# Fsociety_Keyboard_SCH_Main.net
KiCad netlist of a schematic drawn in Altium Designer
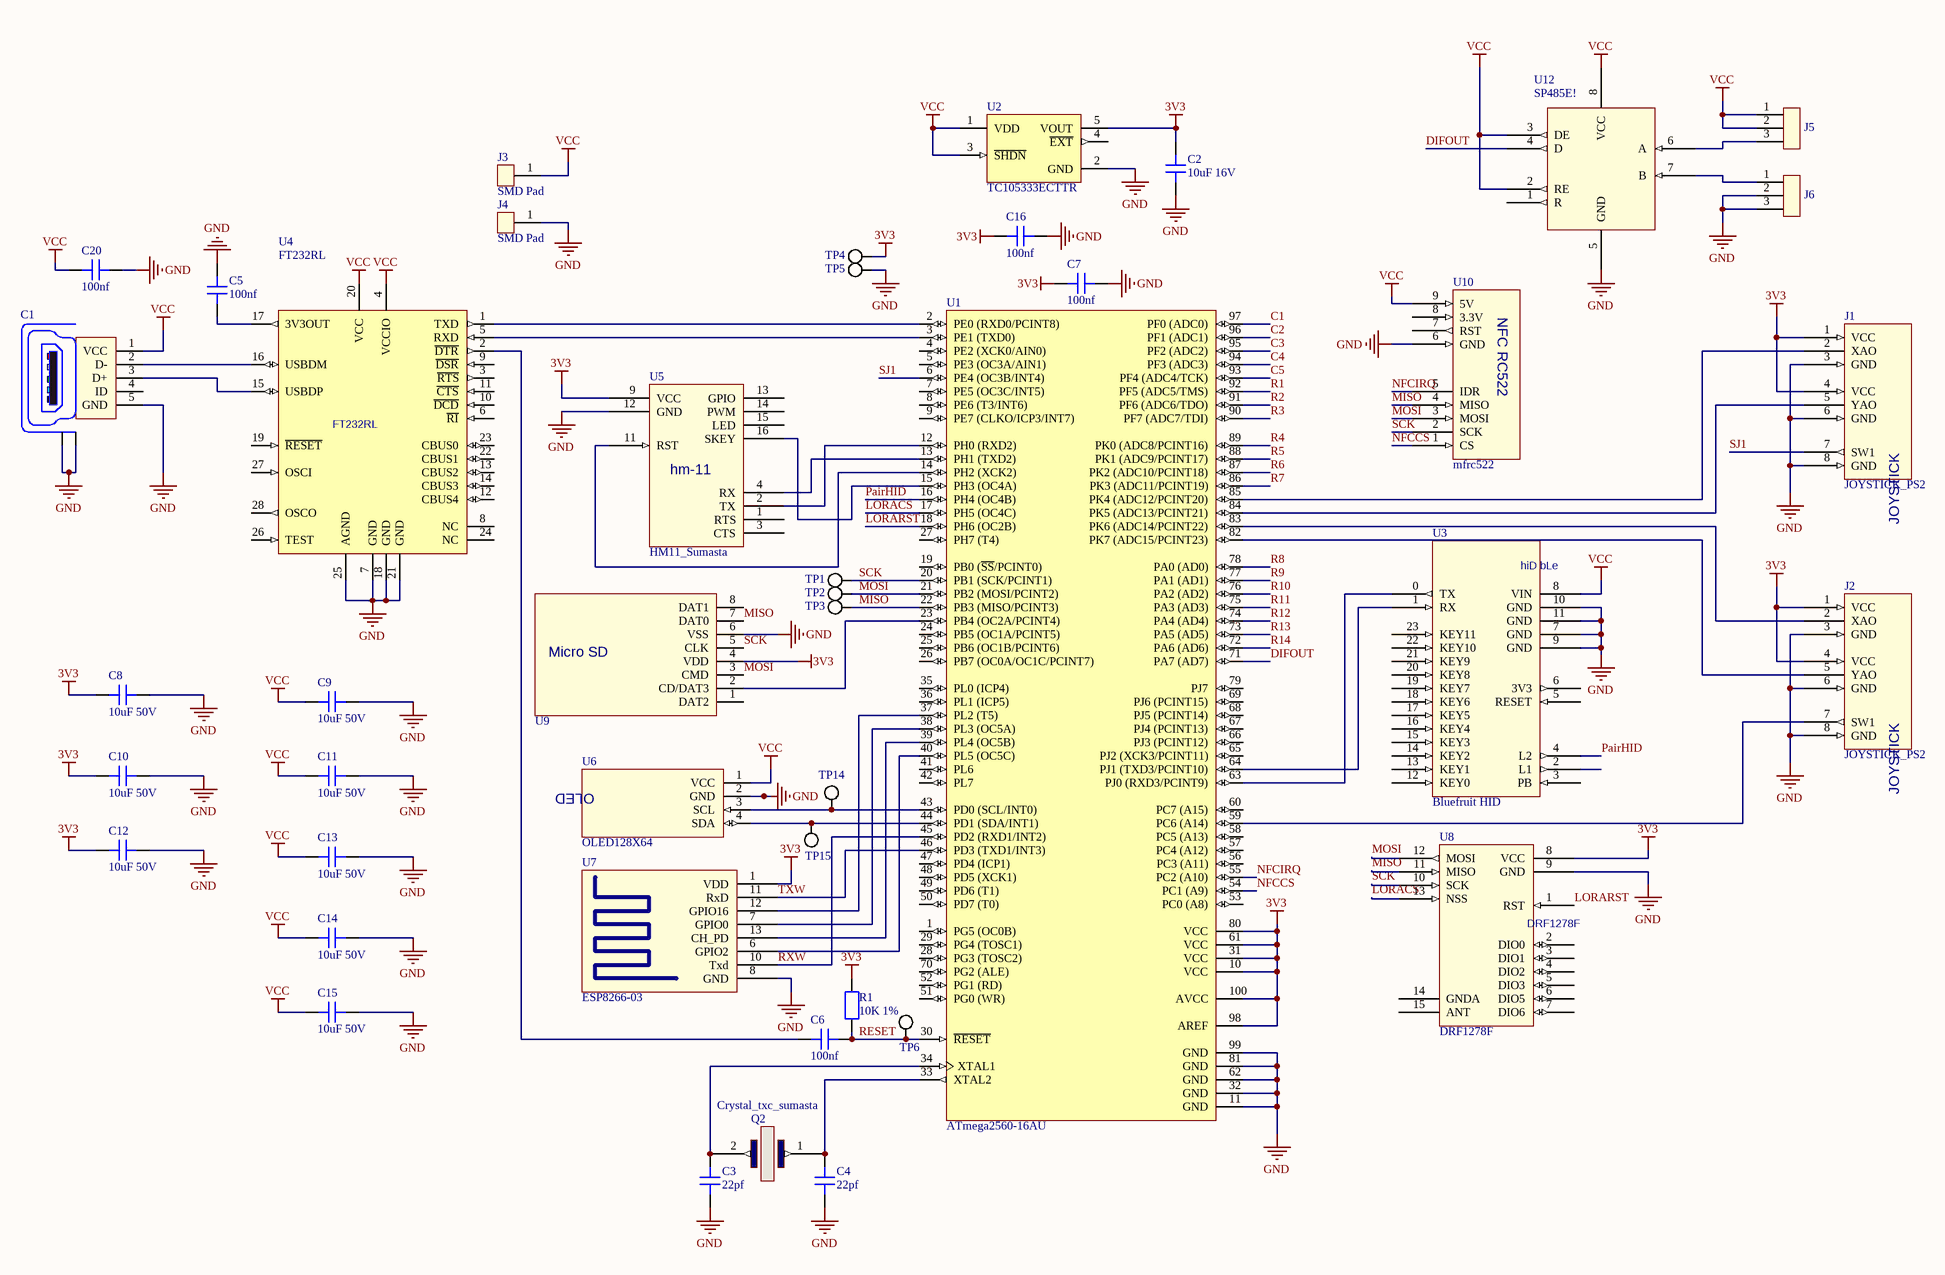
[diagram p0: Fsociety_Keyboard_SCH_Main.SchDoc]

(export (version "E")
  (design (tool "Eeschema 10.0.6"))
  (components
    (comp (ref "C1")
      (value "WR-Communication Connectors 629105150921")
      (footprint "629105150921")
      (description "WR-COM_USB_Micro Type AB_Horizontal_SMT")
      (fields
        (field (name "MANUFACTURER") "Würth Elektronik eiSos GmbH")
        (field (name "PARTNO") "629105150921")
        (field (name "CREATED BY") "Karrer Zheng")
      )
      (libsource (lib "WR-COM_Communication Connectors_rev15f") (part "WR-Communication Connectors 629105150921"))
    )
    (comp (ref "C2")
      (value "10uF 16V")
      (footprint "CAPC1608X08_NR")
      (description "Capacitor 10nF X7R ±10% 50V 0603(1608) SMD")
      (fields (field (name "MAXPARTNUMBER") "10N/50-0603!") (field (name "TOLERANCE") "±10%"))
      (libsource (lib "RENA Vault") (part "CMP-00064-A.5"))
    )
    (comp (ref "C3")
      (value "22pf")
      (footprint "CAPC1608X08_NR")
      (description "Capacitor 10nF X7R ±10% 50V 0603(1608) SMD")
      (fields (field (name "MAXPARTNUMBER") "10N/50-0603!") (field (name "TOLERANCE") "±10%"))
      (libsource (lib "RENA Vault") (part "CMP-00064-A.5"))
    )
    (comp (ref "C4")
      (value "22pf")
      (footprint "CAPC1608X08_NR")
      (description "Capacitor 10nF X7R ±10% 50V 0603(1608) SMD")
      (fields (field (name "MAXPARTNUMBER") "10N/50-0603!") (field (name "TOLERANCE") "±10%"))
      (libsource (lib "RENA Vault") (part "CMP-00064-A.5"))
    )
    (comp (ref "C5")
      (value "100nf")
      (footprint "CAPC1608X08_NR")
      (description "Capacitor 10nF X7R ±10% 50V 0603(1608) SMD")
      (fields (field (name "MAXPARTNUMBER") "10N/50-0603!") (field (name "TOLERANCE") "±10%"))
      (libsource (lib "RENA Vault") (part "CMP-00064-A.5"))
    )
    (comp (ref "C6")
      (value "100nf")
      (footprint "CAPC1608X08_NR")
      (description "Capacitor 10nF X7R ±10% 50V 0603(1608) SMD")
      (fields (field (name "MAXPARTNUMBER") "10N/50-0603!") (field (name "TOLERANCE") "±10%"))
      (libsource (lib "RENA Vault") (part "CMP-00064-A.5"))
    )
    (comp (ref "C7")
      (value "100nf")
      (footprint "CAPC1608X08_NR")
      (description "Capacitor 10nF X7R ±10% 50V 0603(1608) SMD")
      (fields (field (name "MAXPARTNUMBER") "10N/50-0603!") (field (name "TOLERANCE") "±10%"))
      (libsource (lib "RENA Vault") (part "CMP-00064-A.5"))
    )
    (comp (ref "C8")
      (value "10uF 50V")
      (footprint "CAPC3216X09_MW")
      (description "Capacitor 10uF X5R ±20% 50V 1206(3216) SMD")
      (fields (field (name "VOLTAGE") "50V") (field (name "TOLERANCE") "±20%"))
      (libsource (lib "RENA Vault") (part "Cer.Cap"))
    )
    (comp (ref "C9")
      (value "10uF 50V")
      (footprint "CAPC3216X09_MW")
      (description "Capacitor 10uF X5R ±20% 50V 1206(3216) SMD")
      (fields (field (name "VOLTAGE") "50V") (field (name "TOLERANCE") "±20%"))
      (libsource (lib "RENA Vault") (part "Cer.Cap"))
    )
    (comp (ref "C10")
      (value "10uF 50V")
      (footprint "CAPC3216X09_MW")
      (description "Capacitor 10uF X5R ±20% 50V 1206(3216) SMD")
      (fields (field (name "VOLTAGE") "50V") (field (name "TOLERANCE") "±20%"))
      (libsource (lib "RENA Vault") (part "Cer.Cap"))
    )
    (comp (ref "C11")
      (value "10uF 50V")
      (footprint "CAPC3216X09_MW")
      (description "Capacitor 10uF X5R ±20% 50V 1206(3216) SMD")
      (fields (field (name "VOLTAGE") "50V") (field (name "TOLERANCE") "±20%"))
      (libsource (lib "RENA Vault") (part "Cer.Cap"))
    )
    (comp (ref "C12")
      (value "10uF 50V")
      (footprint "CAPC3216X09_MW")
      (description "Capacitor 10uF X5R ±20% 50V 1206(3216) SMD")
      (fields (field (name "VOLTAGE") "50V") (field (name "TOLERANCE") "±20%"))
      (libsource (lib "RENA Vault") (part "Cer.Cap"))
    )
    (comp (ref "C13")
      (value "10uF 50V")
      (footprint "CAPC3216X09_MW")
      (description "Capacitor 10uF X5R ±20% 50V 1206(3216) SMD")
      (fields (field (name "VOLTAGE") "50V") (field (name "TOLERANCE") "±20%"))
      (libsource (lib "RENA Vault") (part "Cer.Cap"))
    )
    (comp (ref "C14")
      (value "10uF 50V")
      (footprint "CAPC3216X09_MW")
      (description "Capacitor 10uF X5R ±20% 50V 1206(3216) SMD")
      (fields (field (name "VOLTAGE") "50V") (field (name "TOLERANCE") "±20%"))
      (libsource (lib "RENA Vault") (part "Cer.Cap"))
    )
    (comp (ref "C15")
      (value "10uF 50V")
      (footprint "CAPC3216X09_MW")
      (description "Capacitor 10uF X5R ±20% 50V 1206(3216) SMD")
      (fields (field (name "VOLTAGE") "50V") (field (name "TOLERANCE") "±20%"))
      (libsource (lib "RENA Vault") (part "Cer.Cap"))
    )
    (comp (ref "C16")
      (value "100nf")
      (footprint "CAPC1608X08_NR")
      (description "Capacitor 10nF X7R ±10% 50V 0603(1608) SMD")
      (fields (field (name "MAXPARTNUMBER") "10N/50-0603!") (field (name "TOLERANCE") "±10%"))
      (libsource (lib "RENA Vault") (part "CMP-00064-A.5"))
    )
    (comp (ref "C20")
      (value "100nf")
      (footprint "CAPC1608X08_NR")
      (description "Capacitor 10nF X7R ±10% 50V 0603(1608) SMD")
      (fields (field (name "MAXPARTNUMBER") "10N/50-0603!") (field (name "TOLERANCE") "±10%"))
      (libsource (lib "RENA Vault") (part "CMP-00064-A.5"))
    )
    (comp (ref "J1")
      (value "JOYSTICK_PS2")
      (footprint "JOYSTICK")
      (libsource (lib "Sumasta_new") (part "JOYSTICK_PS2"))
    )
    (comp (ref "J2")
      (value "JOYSTICK_PS2")
      (footprint "JOYSTICK")
      (libsource (lib "Sumasta_new") (part "JOYSTICK_PS2"))
    )
    (comp (ref "J3")
      (value "SMD Pad")
      (footprint "CON_SMDPAD_10X5")
      (description "SMD PAD DIFFERENT SHAPES")
      (fields (field (name "MAXPARTNUMBER") "PAD_SMD!#"))
      (libsource (lib "RENA Vault") (part "CMP-00667-A.10"))
    )
    (comp (ref "J4")
      (value "SMD Pad")
      (footprint "CON_SMDPAD_10X5")
      (description "SMD PAD DIFFERENT SHAPES")
      (fields (field (name "MAXPARTNUMBER") "PAD_SMD!#"))
      (libsource (lib "RENA Vault") (part "CMP-00667-A.10"))
    )
    (comp (ref "J5")
      (value "BB02-HA031-KB1-100/33/D1")
      (footprint "FCI_77315-134-03LF")
      (description "Unshrouded header 3-pin right angle")
      (fields (field (name "MAXPARTNUMBER") "CON-BB02-HA031"))
      (libsource (lib "RENA Vault") (part "CMP-01396-A.1"))
    )
    (comp (ref "J6")
      (value "BB02-HA031-KB1-100/33/D1")
      (footprint "FCI_77315-134-03LF")
      (description "Unshrouded header 3-pin right angle")
      (fields (field (name "MAXPARTNUMBER") "CON-BB02-HA031"))
      (libsource (lib "RENA Vault") (part "CMP-01396-A.1"))
    )
    (comp (ref "Q2")
      (value "Crystal_txc_sumasta")
      (footprint "Crystal_txc_sumasta")
      (libsource (lib "Sumasta_new") (part "Crystal_txc_sumasta"))
    )
    (comp (ref "R1")
      (value "10K 1%")
      (footprint "RESC1608X06_NR")
      (description "10K  0.1W 1% 0603(1608 Metric) SMD")
      (fields (field (name "MAXPARTNUMBER") "10K-0603!") (field (name "POWER") "0.1W"))
      (libsource (lib "RENA Vault") (part "RES"))
    )
    (comp (ref "TP1")
      (value "TP")
      (footprint "TESTPAD-2MM")
      (description "TESTPOINT")
      (fields (field (name "MAXPARTNUMBER") "TP#"))
      (libsource (lib "RENA Vault") (part "CMP-00759-A.11"))
    )
    (comp (ref "TP2")
      (value "TP")
      (footprint "TESTPAD-2MM")
      (description "TESTPOINT")
      (fields (field (name "MAXPARTNUMBER") "TP#"))
      (libsource (lib "RENA Vault") (part "CMP-00759-A.11"))
    )
    (comp (ref "TP3")
      (value "TP")
      (footprint "TESTPAD-2MM")
      (description "TESTPOINT")
      (fields (field (name "MAXPARTNUMBER") "TP#"))
      (libsource (lib "RENA Vault") (part "CMP-00759-A.11"))
    )
    (comp (ref "TP4")
      (value "TP")
      (footprint "TESTPAD-2MM")
      (description "TESTPOINT")
      (fields (field (name "MAXPARTNUMBER") "TP#"))
      (libsource (lib "RENA Vault") (part "CMP-00759-A.11"))
    )
    (comp (ref "TP5")
      (value "TP")
      (footprint "TESTPAD-2MM")
      (description "TESTPOINT")
      (fields (field (name "MAXPARTNUMBER") "TP#"))
      (libsource (lib "RENA Vault") (part "CMP-00759-A.11"))
    )
    (comp (ref "TP6")
      (value "TP")
      (footprint "TESTPAD-2MM")
      (description "TESTPOINT")
      (fields (field (name "MAXPARTNUMBER") "TP#"))
      (libsource (lib "RENA Vault") (part "CMP-00759-A.11"))
    )
    (comp (ref "TP14")
      (value "TP")
      (footprint "TESTPAD-2MM")
      (description "TESTPOINT")
      (fields (field (name "MAXPARTNUMBER") "TP#"))
      (libsource (lib "RENA Vault") (part "CMP-00759-A.11"))
    )
    (comp (ref "TP15")
      (value "TP")
      (footprint "TESTPAD-2MM")
      (description "TESTPOINT")
      (fields (field (name "MAXPARTNUMBER") "TP#"))
      (libsource (lib "RENA Vault") (part "CMP-00759-A.11"))
    )
    (comp (ref "U1")
      (value "ATmega2560-16AU")
      (footprint "100A_N")
      (libsource (lib "Atmel Microcontroller megaAVR") (part "ATmega2560-16AU"))
    )
    (comp (ref "U2")
      (value "TC105333ECTTR")
      (footprint "SOT-23-CT5_N")
      (fields (field (name "MANUFACTURER") "Microchip"))
      (libsource (lib "Microchip Power Management Switching Regulator") (part "TC105333ECTTR"))
    )
    (comp (ref "U3")
      (value "Bluefruit HID")
      (footprint "BLuefruit HID")
      (libsource (lib "Sumasta_new") (part "Bluefruit HID"))
    )
    (comp (ref "U4") (value "FT232RL") (footprint "SSPO28") (libsource (lib "Sumasta_new") (part "FT232RL")))
    (comp (ref "U5")
      (value "HM11_Sumasta")
      (footprint "HM11_Sumasta")
      (libsource (lib "Sumasta_new") (part "HM11_Sumasta"))
    )
    (comp (ref "U6")
      (value "OLED128X64")
      (footprint "OLED128x64")
      (libsource (lib "Sumasta_new") (part "OLED128X64"))
    )
    (comp (ref "U7")
      (value "ESP8266-03")
      (footprint "ESP8266-03")
      (libsource (lib "Sumasta_new") (part "ESP8266-03"))
    )
    (comp (ref "U8")
      (value "DRF1278F")
      (footprint "DRF1278F")
      (libsource (lib "Sumasta_new") (part "DRF1278F"))
    )
    (comp (ref "U9")
      (value "Micro SD Connector - Hinge")
      (footprint "Micro SD Socket")
      (libsource (lib "Sumasta_new") (part "MicroSD Socket"))
    )
    (comp (ref "U10")
      (value "mfrc522")
      (footprint "MFRC522")
      (libsource (lib "Sumasta_new") (part "mfrc522"))
    )
    (comp (ref "U12")
      (value "RS485 Buffer Transceiver")
      (footprint "SOIC127P600-8N")
      (fields (field (name "MAXPARTNUMBER") "SP485E!"))
      (libsource (lib "Sumasta_new") (part "SN75176"))
    )
  )
  (nets
    (net (code "1") (name "/C1") (class "Default")
      (node (ref "U1") (pin "97") (pinfunction "PF0_(ADC0)_97") (pintype "bidirectional"))
    )
    (net (code "2") (name "/C2") (class "Default")
      (node (ref "U1") (pin "96") (pinfunction "PF1_(ADC1)_96") (pintype "bidirectional"))
    )
    (net (code "3") (name "/C3") (class "Default")
      (node (ref "U1") (pin "95") (pinfunction "PF2_(ADC2)_95") (pintype "bidirectional"))
    )
    (net (code "4") (name "/C4") (class "Default")
      (node (ref "U1") (pin "94") (pinfunction "PF3_(ADC3)_94") (pintype "bidirectional"))
    )
    (net (code "5") (name "/C5") (class "Default")
      (node (ref "U1") (pin "93") (pinfunction "PF4_(ADC4/TCK)_93") (pintype "bidirectional"))
    )
    (net (code "6") (name "/DIFOUT") (class "Default")
      (node (ref "U1") (pin "71") (pinfunction "PA7_(AD7)_71") (pintype "bidirectional"))
      (node (ref "U12") (pin "4") (pinfunction "D_4") (pintype "output"))
    )
    (net (code "7") (name "/LORACS") (class "Default")
      (node (ref "U1") (pin "17") (pinfunction "PH5_(OC4C)_17") (pintype "bidirectional"))
      (node (ref "U8") (pin "13") (pinfunction "NSS_13") (pintype "input"))
    )
    (net (code "8") (name "/LORARST") (class "Default")
      (node (ref "U1") (pin "18") (pinfunction "PH6_(OC2B)_18") (pintype "bidirectional"))
      (node (ref "U8") (pin "1") (pinfunction "RST_1") (pintype "input"))
    )
    (net (code "9") (name "/MISO") (class "Default")
      (node (ref "TP3") (pin "1") (pinfunction "1_1") (pintype "passive"))
      (node (ref "U1") (pin "22") (pinfunction "PB3_(MISO/PCINT3)_22") (pintype "bidirectional"))
      (node (ref "U10") (pin "4") (pinfunction "MISO_4") (pintype "input"))
      (node (ref "U8") (pin "11") (pinfunction "MISO_11") (pintype "input"))
      (node (ref "U9") (pin "7") (pinfunction "DAT0_7") (pintype "passive"))
    )
    (net (code "10") (name "/MOSI") (class "Default")
      (node (ref "TP2") (pin "1") (pinfunction "1_1") (pintype "passive"))
      (node (ref "U1") (pin "21") (pinfunction "PB2_(MOSI/PCINT2)_21") (pintype "bidirectional"))
      (node (ref "U10") (pin "3") (pinfunction "MOSI_3") (pintype "input"))
      (node (ref "U8") (pin "12") (pinfunction "MOSI_12") (pintype "output"))
      (node (ref "U9") (pin "3") (pinfunction "CMD_3") (pintype "passive"))
    )
    (net (code "11") (name "/NFCCS") (class "Default")
      (node (ref "U1") (pin "54") (pinfunction "PC1_(A9)_54") (pintype "bidirectional"))
      (node (ref "U10") (pin "1") (pinfunction "CS_1") (pintype "input"))
    )
    (net (code "12") (name "/NFCIRQ") (class "Default")
      (node (ref "U1") (pin "55") (pinfunction "PC2_(A10)_55") (pintype "bidirectional"))
      (node (ref "U10") (pin "5") (pinfunction "IDR_5") (pintype "passive"))
    )
    (net (code "13") (name "/PairHID") (class "Default")
      (node (ref "U1") (pin "16") (pinfunction "PH4_(OC4B)_16") (pintype "bidirectional"))
      (node (ref "U3") (pin "4") (pinfunction "L2_4") (pintype "output"))
    )
    (net (code "14") (name "/R1") (class "Default")
      (node (ref "U1") (pin "92") (pinfunction "PF5_(ADC5/TMS)_92") (pintype "bidirectional"))
    )
    (net (code "15") (name "/R2") (class "Default")
      (node (ref "U1") (pin "91") (pinfunction "PF6_(ADC6/TDO)_91") (pintype "bidirectional"))
    )
    (net (code "16") (name "/R3") (class "Default")
      (node (ref "U1") (pin "90") (pinfunction "PF7_(ADC7/TDI)_90") (pintype "bidirectional"))
    )
    (net (code "17") (name "/R4") (class "Default")
      (node (ref "U1") (pin "89") (pinfunction "PK0_(ADC8/PCINT16)_89") (pintype "bidirectional"))
    )
    (net (code "18") (name "/R5") (class "Default")
      (node (ref "U1") (pin "88") (pinfunction "PK1_(ADC9/PCINT17)_88") (pintype "bidirectional"))
    )
    (net (code "19") (name "/R6") (class "Default")
      (node (ref "U1") (pin "87") (pinfunction "PK2_(ADC10/PCINT18)_87") (pintype "bidirectional"))
    )
    (net (code "20") (name "/R7") (class "Default")
      (node (ref "U1") (pin "86") (pinfunction "PK3_(ADC11/PCINT19)_86") (pintype "bidirectional"))
    )
    (net (code "21") (name "/R8") (class "Default")
      (node (ref "U1") (pin "78") (pinfunction "PA0_(AD0)_78") (pintype "bidirectional"))
    )
    (net (code "22") (name "/R9") (class "Default")
      (node (ref "U1") (pin "77") (pinfunction "PA1_(AD1)_77") (pintype "bidirectional"))
    )
    (net (code "23") (name "/R10") (class "Default")
      (node (ref "U1") (pin "76") (pinfunction "PA2_(AD2)_76") (pintype "bidirectional"))
    )
    (net (code "24") (name "/R11") (class "Default")
      (node (ref "U1") (pin "75") (pinfunction "PA3_(AD3)_75") (pintype "bidirectional"))
    )
    (net (code "25") (name "/R12") (class "Default")
      (node (ref "U1") (pin "74") (pinfunction "PA4_(AD4)_74") (pintype "bidirectional"))
    )
    (net (code "26") (name "/R13") (class "Default")
      (node (ref "U1") (pin "73") (pinfunction "PA5_(AD5)_73") (pintype "bidirectional"))
    )
    (net (code "27") (name "/R14") (class "Default")
      (node (ref "U1") (pin "72") (pinfunction "PA6_(AD6)_72") (pintype "bidirectional"))
    )
    (net (code "28") (name "/RESET") (class "Default")
      (node (ref "C6") (pin "2") (pinfunction "2_2") (pintype "passive"))
      (node (ref "R1") (pin "1") (pinfunction "1_1") (pintype "passive"))
      (node (ref "TP6") (pin "1") (pinfunction "1_1") (pintype "passive"))
      (node (ref "U1") (pin "30") (pinfunction "~{RESET}_30") (pintype "input"))
    )
    (net (code "29") (name "/RXW") (class "Default")
      (node (ref "U1") (pin "45") (pinfunction "PD2_(RXD1/INT2)_45") (pintype "bidirectional"))
      (node (ref "U7") (pin "10") (pinfunction "Txd_10") (pintype "passive"))
    )
    (net (code "30") (name "/SCK") (class "Default")
      (node (ref "TP1") (pin "1") (pinfunction "1_1") (pintype "passive"))
      (node (ref "U1") (pin "20") (pinfunction "PB1_(SCK/PCINT1)_20") (pintype "bidirectional"))
      (node (ref "U10") (pin "2") (pinfunction "SCK_2") (pintype "passive"))
      (node (ref "U8") (pin "10") (pinfunction "SCK_10") (pintype "input"))
      (node (ref "U9") (pin "5") (pinfunction "CLK_5") (pintype "passive"))
    )
    (net (code "31") (name "/SJ1") (class "Default")
      (node (ref "J1") (pin "7") (pinfunction "SW1_7") (pintype "output"))
      (node (ref "U1") (pin "6") (pinfunction "PE4_(OC3B/INT4)_6") (pintype "bidirectional"))
    )
    (net (code "32") (name "/TXW") (class "Default")
      (node (ref "U1") (pin "46") (pinfunction "PD3_(TXD1/INT3)_46") (pintype "bidirectional"))
      (node (ref "U7") (pin "11") (pinfunction "RxD_11") (pintype "passive"))
    )
    (net (code "33") (name "3V3") (class "Default")
      (node (ref "C10") (pin "1") (pinfunction "1_1") (pintype "passive"))
      (node (ref "C12") (pin "1") (pinfunction "1_1") (pintype "passive"))
      (node (ref "C16") (pin "1") (pinfunction "1_1") (pintype "passive"))
      (node (ref "C2") (pin "2") (pinfunction "2_2") (pintype "passive"))
      (node (ref "C7") (pin "1") (pinfunction "1_1") (pintype "passive"))
      (node (ref "C8") (pin "1") (pinfunction "1_1") (pintype "passive"))
      (node (ref "J1") (pin "1") (pinfunction "VCC_1") (pintype "input"))
      (node (ref "J1") (pin "4") (pinfunction "VCC_4") (pintype "input"))
      (node (ref "J2") (pin "1") (pinfunction "VCC_1") (pintype "input"))
      (node (ref "J2") (pin "4") (pinfunction "VCC_4") (pintype "input"))
      (node (ref "R1") (pin "2") (pinfunction "2_2") (pintype "passive"))
      (node (ref "TP4") (pin "1") (pinfunction "1_1") (pintype "passive"))
      (node (ref "U1") (pin "10") (pinfunction "VCC_10") (pintype "power_in"))
      (node (ref "U1") (pin "100") (pinfunction "AVCC_100") (pintype "power_in"))
      (node (ref "U1") (pin "31") (pinfunction "VCC_31") (pintype "power_in"))
      (node (ref "U1") (pin "61") (pinfunction "VCC_61") (pintype "power_in"))
      (node (ref "U1") (pin "80") (pinfunction "VCC_80") (pintype "power_in"))
      (node (ref "U1") (pin "98") (pinfunction "AREF_98") (pintype "power_in"))
      (node (ref "U2") (pin "5") (pinfunction "VOUT_5") (pintype "power_in"))
      (node (ref "U5") (pin "9") (pinfunction "VCC_9") (pintype "power_in"))
      (node (ref "U7") (pin "1") (pinfunction "VDD_1") (pintype "passive"))
      (node (ref "U8") (pin "8") (pinfunction "VCC_8") (pintype "power_in"))
      (node (ref "U9") (pin "4") (pinfunction "VDD_4") (pintype "passive"))
    )
    (net (code "34") (name "GND") (class "Default")
      (node (ref "C1") (pin "5") (pinfunction "GND_5") (pintype "passive"))
      (node (ref "C1") (pin "Z1") (pinfunction "Shield_Z1") (pintype "passive"))
      (node (ref "C1") (pin "Z2") (pinfunction "Shield_Z2") (pintype "passive"))
      (node (ref "C10") (pin "2") (pinfunction "2_2") (pintype "passive"))
      (node (ref "C11") (pin "2") (pinfunction "2_2") (pintype "passive"))
      (node (ref "C12") (pin "2") (pinfunction "2_2") (pintype "passive"))
      (node (ref "C13") (pin "2") (pinfunction "2_2") (pintype "passive"))
      (node (ref "C14") (pin "2") (pinfunction "2_2") (pintype "passive"))
      (node (ref "C15") (pin "2") (pinfunction "2_2") (pintype "passive"))
      (node (ref "C16") (pin "2") (pinfunction "2_2") (pintype "passive"))
      (node (ref "C2") (pin "1") (pinfunction "1_1") (pintype "passive"))
      (node (ref "C20") (pin "1") (pinfunction "1_1") (pintype "passive"))
      (node (ref "C3") (pin "1") (pinfunction "1_1") (pintype "passive"))
      (node (ref "C4") (pin "1") (pinfunction "1_1") (pintype "passive"))
      (node (ref "C5") (pin "2") (pinfunction "2_2") (pintype "passive"))
      (node (ref "C7") (pin "2") (pinfunction "2_2") (pintype "passive"))
      (node (ref "C8") (pin "2") (pinfunction "2_2") (pintype "passive"))
      (node (ref "C9") (pin "2") (pinfunction "2_2") (pintype "passive"))
      (node (ref "J1") (pin "3") (pinfunction "GND_3") (pintype "input"))
      (node (ref "J1") (pin "6") (pinfunction "GND_6") (pintype "input"))
      (node (ref "J1") (pin "8") (pinfunction "GND_8") (pintype "input"))
      (node (ref "J2") (pin "3") (pinfunction "GND_3") (pintype "input"))
      (node (ref "J2") (pin "6") (pinfunction "GND_6") (pintype "input"))
      (node (ref "J2") (pin "8") (pinfunction "GND_8") (pintype "input"))
      (node (ref "J4") (pin "1") (pintype "passive"))
      (node (ref "J6") (pin "2") (pintype "passive"))
      (node (ref "J6") (pin "3") (pintype "passive"))
      (node (ref "TP5") (pin "1") (pinfunction "1_1") (pintype "passive"))
      (node (ref "U1") (pin "11") (pinfunction "GND_11") (pintype "power_in"))
      (node (ref "U1") (pin "32") (pinfunction "GND_32") (pintype "power_in"))
      (node (ref "U1") (pin "62") (pinfunction "GND_62") (pintype "power_in"))
      (node (ref "U1") (pin "81") (pinfunction "GND_81") (pintype "power_in"))
      (node (ref "U1") (pin "99") (pinfunction "GND_99") (pintype "power_in"))
      (node (ref "U10") (pin "6") (pinfunction "GND_6") (pintype "input"))
      (node (ref "U12") (pin "5") (pinfunction "GND_5") (pintype "power_in"))
      (node (ref "U2") (pin "2") (pinfunction "GND_2") (pintype "power_in"))
      (node (ref "U3") (pin "10") (pinfunction "GND_10") (pintype "power_in"))
      (node (ref "U3") (pin "11") (pinfunction "GND_11") (pintype "power_in"))
      (node (ref "U3") (pin "7") (pinfunction "GND_7") (pintype "power_in"))
      (node (ref "U3") (pin "9") (pinfunction "GND_9") (pintype "power_in"))
      (node (ref "U4") (pin "18") (pinfunction "GND_18") (pintype "power_in"))
      (node (ref "U4") (pin "21") (pinfunction "GND_21") (pintype "power_in"))
      (node (ref "U4") (pin "25") (pinfunction "AGND_25") (pintype "power_in"))
      (node (ref "U4") (pin "7") (pinfunction "GND_7") (pintype "power_in"))
      (node (ref "U5") (pin "12") (pinfunction "GND_12") (pintype "power_in"))
      (node (ref "U6") (pin "2") (pinfunction "GND_2") (pintype "power_in"))
      (node (ref "U7") (pin "8") (pinfunction "GND_8") (pintype "passive"))
      (node (ref "U8") (pin "9") (pinfunction "GND_9") (pintype "power_in"))
      (node (ref "U9") (pin "6") (pinfunction "VSS_6") (pintype "passive"))
    )
    (net (code "35") (name "Net-(C1-D+)") (class "Default")
      (node (ref "C1") (pin "3") (pinfunction "D+_3") (pintype "passive"))
      (node (ref "U4") (pin "15") (pinfunction "USBDP_15") (pintype "bidirectional"))
    )
    (net (code "36") (name "Net-(C1-D-)") (class "Default")
      (node (ref "C1") (pin "2") (pinfunction "D-_2") (pintype "passive"))
      (node (ref "U4") (pin "16") (pinfunction "USBDM_16") (pintype "bidirectional"))
    )
    (net (code "37") (name "Net-(J1-XAO)") (class "Default")
      (node (ref "J1") (pin "2") (pinfunction "XAO_2") (pintype "passive"))
      (node (ref "U1") (pin "85") (pinfunction "PK4_(ADC12/PCINT20)_85") (pintype "bidirectional"))
    )
    (net (code "38") (name "Net-(J1-YAO)") (class "Default")
      (node (ref "J1") (pin "5") (pinfunction "YAO_5") (pintype "passive"))
      (node (ref "U1") (pin "84") (pinfunction "PK5_(ADC13/PCINT21)_84") (pintype "bidirectional"))
    )
    (net (code "39") (name "Net-(J2-SW1)") (class "Default")
      (node (ref "J2") (pin "7") (pinfunction "SW1_7") (pintype "output"))
      (node (ref "U1") (pin "59") (pinfunction "PC6_(A14)_59") (pintype "bidirectional"))
    )
    (net (code "40") (name "Net-(J2-XAO)") (class "Default")
      (node (ref "J2") (pin "2") (pinfunction "XAO_2") (pintype "passive"))
      (node (ref "U1") (pin "83") (pinfunction "PK6_(ADC14/PCINT22)_83") (pintype "bidirectional"))
    )
    (net (code "41") (name "Net-(J2-YAO)") (class "Default")
      (node (ref "J2") (pin "5") (pinfunction "YAO_5") (pintype "passive"))
      (node (ref "U1") (pin "82") (pinfunction "PK7_(ADC15/PCINT23)_82") (pintype "bidirectional"))
    )
    (net (code "42") (name "Net-(U1-PB4_(OC2A{slash}PCINT4))") (class "Default")
      (node (ref "U1") (pin "23") (pinfunction "PB4_(OC2A/PCINT4)_23") (pintype "bidirectional"))
      (node (ref "U9") (pin "2") (pinfunction "CD/DAT3_2") (pintype "passive"))
    )
    (net (code "43") (name "Net-(U1-PD0_(SCL{slash}INT0))") (class "Default")
      (node (ref "TP14") (pin "1") (pinfunction "1_1") (pintype "passive"))
      (node (ref "U1") (pin "43") (pinfunction "PD0_(SCL/INT0)_43") (pintype "bidirectional"))
      (node (ref "U6") (pin "3") (pinfunction "SCL_3") (pintype "input"))
    )
    (net (code "44") (name "Net-(U1-PD1_(SDA{slash}INT1))") (class "Default")
      (node (ref "TP15") (pin "1") (pinfunction "1_1") (pintype "passive"))
      (node (ref "U1") (pin "44") (pinfunction "PD1_(SDA/INT1)_44") (pintype "bidirectional"))
      (node (ref "U6") (pin "4") (pinfunction "SDA_4") (pintype "bidirectional"))
    )
    (net (code "45") (name "Net-(U1-PE0_(RXD0{slash}PCINT8))") (class "Default")
      (node (ref "U1") (pin "2") (pinfunction "PE0_(RXD0/PCINT8)_2") (pintype "bidirectional"))
      (node (ref "U4") (pin "1") (pinfunction "TXD_1") (pintype "output"))
    )
    (net (code "46") (name "Net-(U1-PE1_(TXD0))") (class "Default")
      (node (ref "U1") (pin "3") (pinfunction "PE1_(TXD0)_3") (pintype "bidirectional"))
      (node (ref "U4") (pin "5") (pinfunction "RXD_5") (pintype "input"))
    )
    (net (code "47") (name "Net-(U1-PH0_(RXD2))") (class "Default")
      (node (ref "U1") (pin "12") (pinfunction "PH0_(RXD2)_12") (pintype "bidirectional"))
      (node (ref "U5") (pin "2") (pinfunction "TX_2") (pintype "passive"))
    )
    (net (code "48") (name "Net-(U1-PH1_(TXD2))") (class "Default")
      (node (ref "U1") (pin "13") (pinfunction "PH1_(TXD2)_13") (pintype "bidirectional"))
      (node (ref "U5") (pin "4") (pinfunction "RX_4") (pintype "passive"))
    )
    (net (code "49") (name "Net-(U1-PH2_(XCK2))") (class "Default")
      (node (ref "U1") (pin "14") (pinfunction "PH2_(XCK2)_14") (pintype "bidirectional"))
      (node (ref "U5") (pin "11") (pinfunction "RST_11") (pintype "input"))
    )
    (net (code "50") (name "Net-(U1-PH3_(OC4A))") (class "Default")
      (node (ref "U1") (pin "15") (pinfunction "PH3_(OC4A)_15") (pintype "bidirectional"))
      (node (ref "U5") (pin "16") (pinfunction "SKEY_16") (pintype "passive"))
    )
    (net (code "51") (name "Net-(U1-PJ0_(RXD3{slash}PCINT9))") (class "Default")
      (node (ref "U1") (pin "63") (pinfunction "PJ0_(RXD3/PCINT9)_63") (pintype "bidirectional"))
      (node (ref "U3") (pin "0") (pinfunction "TX_0") (pintype "output"))
    )
    (net (code "52") (name "Net-(U1-PJ1_(TXD3{slash}PCINT10))") (class "Default")
      (node (ref "U1") (pin "64") (pinfunction "PJ1_(TXD3/PCINT10)_64") (pintype "bidirectional"))
      (node (ref "U3") (pin "1") (pinfunction "RX_1") (pintype "input"))
    )
    (net (code "53") (name "Net-(U1-PL2_(T5))") (class "Default")
      (node (ref "U1") (pin "37") (pinfunction "PL2_(T5)_37") (pintype "bidirectional"))
      (node (ref "U7") (pin "12") (pinfunction "GPIO16_12") (pintype "passive"))
    )
    (net (code "54") (name "Net-(U1-PL3_(OC5A))") (class "Default")
      (node (ref "U1") (pin "38") (pinfunction "PL3_(OC5A)_38") (pintype "bidirectional"))
      (node (ref "U7") (pin "7") (pinfunction "GPIO0_7") (pintype "passive"))
    )
    (net (code "55") (name "Net-(U1-PL4_(OC5B))") (class "Default")
      (node (ref "U1") (pin "39") (pinfunction "PL4_(OC5B)_39") (pintype "bidirectional"))
      (node (ref "U7") (pin "13") (pinfunction "CH_PD_13") (pintype "passive"))
    )
    (net (code "56") (name "Net-(U1-PL5_(OC5C))") (class "Default")
      (node (ref "U1") (pin "40") (pinfunction "PL5_(OC5C)_40") (pintype "bidirectional"))
      (node (ref "U7") (pin "6") (pinfunction "GPIO2_6") (pintype "passive"))
    )
    (net (code "57") (name "Net-(U1-XTAL1)") (class "Default")
      (node (ref "C3") (pin "2") (pinfunction "2_2") (pintype "passive"))
      (node (ref "Q2") (pin "2") (pinfunction "2_2") (pintype "output"))
      (node (ref "U1") (pin "34") (pinfunction "XTAL1_34") (pintype "input"))
    )
    (net (code "58") (name "Net-(U1-XTAL2)") (class "Default")
      (node (ref "C4") (pin "2") (pinfunction "2_2") (pintype "passive"))
      (node (ref "Q2") (pin "1") (pinfunction "1_1") (pintype "output"))
      (node (ref "U1") (pin "33") (pinfunction "XTAL2_33") (pintype "output"))
    )
    (net (code "59") (name "Net-(U4-3V3OUT)") (class "Default")
      (node (ref "C5") (pin "1") (pinfunction "1_1") (pintype "passive"))
      (node (ref "U4") (pin "17") (pinfunction "3V3OUT_17") (pintype "output"))
    )
    (net (code "60") (name "Net-(U4-~{DTR})") (class "Default")
      (node (ref "C6") (pin "1") (pinfunction "1_1") (pintype "passive"))
      (node (ref "U4") (pin "2") (pinfunction "~{DTR}_2") (pintype "output"))
    )
    (net (code "61") (name "Net-(U12-A)") (class "Default")
      (node (ref "J5") (pin "3") (pintype "passive"))
      (node (ref "U12") (pin "6") (pinfunction "A_6") (pintype "input"))
    )
    (net (code "62") (name "Net-(U12-B)") (class "Default")
      (node (ref "J6") (pin "1") (pintype "passive"))
      (node (ref "U12") (pin "7") (pinfunction "B_7") (pintype "input"))
    )
    (net (code "63") (name "VCC") (class "Default")
      (node (ref "C1") (pin "1") (pinfunction "VCC_1") (pintype "passive"))
      (node (ref "C11") (pin "1") (pinfunction "1_1") (pintype "passive"))
      (node (ref "C13") (pin "1") (pinfunction "1_1") (pintype "passive"))
      (node (ref "C14") (pin "1") (pinfunction "1_1") (pintype "passive"))
      (node (ref "C15") (pin "1") (pinfunction "1_1") (pintype "passive"))
      (node (ref "C20") (pin "2") (pinfunction "2_2") (pintype "passive"))
      (node (ref "C9") (pin "1") (pinfunction "1_1") (pintype "passive"))
      (node (ref "J3") (pin "1") (pintype "passive"))
      (node (ref "J5") (pin "1") (pintype "passive"))
      (node (ref "J5") (pin "2") (pintype "passive"))
      (node (ref "U10") (pin "9") (pinfunction "5V_9") (pintype "input"))
      (node (ref "U12") (pin "2") (pinfunction "RE_2") (pintype "output"))
      (node (ref "U12") (pin "3") (pinfunction "DE_3") (pintype "output"))
      (node (ref "U12") (pin "8") (pinfunction "VCC_8") (pintype "power_in"))
      (node (ref "U2") (pin "1") (pinfunction "VDD_1") (pintype "power_in"))
      (node (ref "U2") (pin "3") (pinfunction "~{SHDN}_3") (pintype "input"))
      (node (ref "U3") (pin "8") (pinfunction "VIN_8") (pintype "power_in"))
      (node (ref "U4") (pin "20") (pinfunction "VCC_20") (pintype "power_in"))
      (node (ref "U4") (pin "4") (pinfunction "VCCIO_4") (pintype "power_in"))
      (node (ref "U6") (pin "1") (pinfunction "VCC_1") (pintype "power_in"))
    )
    (net (code "64") (name "unconnected-(C1-ID-Pad4)") (class "Default")
      (node (ref "C1") (pin "4") (pinfunction "ID_4") (pintype "passive"))
    )
    (net (code "65") (name "unconnected-(U1-PB0_(~{SS}{slash}PCINT0)-Pad19)") (class "Default")
      (node (ref "U1") (pin "19") (pinfunction "PB0_(~{SS}/PCINT0)_19") (pintype "bidirectional"))
    )
    (net (code "66") (name "unconnected-(U1-PB5_(OC1A{slash}PCINT5)-Pad24)") (class "Default")
      (node (ref "U1") (pin "24") (pinfunction "PB5_(OC1A/PCINT5)_24") (pintype "bidirectional"))
    )
    (net (code "67") (name "unconnected-(U1-PB6_(OC1B{slash}PCINT6)-Pad25)") (class "Default")
      (node (ref "U1") (pin "25") (pinfunction "PB6_(OC1B/PCINT6)_25") (pintype "bidirectional"))
    )
    (net (code "68") (name "unconnected-(U1-PB7_(OC0A{slash}OC1C{slash}PCINT7)-Pad26)") (class "Default")
      (node (ref "U1") (pin "26") (pinfunction "PB7_(OC0A/OC1C/PCINT7)_26") (pintype "bidirectional"))
    )
    (net (code "69") (name "unconnected-(U1-PC0_(A8)-Pad53)") (class "Default")
      (node (ref "U1") (pin "53") (pinfunction "PC0_(A8)_53") (pintype "bidirectional"))
    )
    (net (code "70") (name "unconnected-(U1-PC3_(A11)-Pad56)") (class "Default")
      (node (ref "U1") (pin "56") (pinfunction "PC3_(A11)_56") (pintype "bidirectional"))
    )
    (net (code "71") (name "unconnected-(U1-PC4_(A12)-Pad57)") (class "Default")
      (node (ref "U1") (pin "57") (pinfunction "PC4_(A12)_57") (pintype "bidirectional"))
    )
    (net (code "72") (name "unconnected-(U1-PC5_(A13)-Pad58)") (class "Default")
      (node (ref "U1") (pin "58") (pinfunction "PC5_(A13)_58") (pintype "bidirectional"))
    )
    (net (code "73") (name "unconnected-(U1-PC7_(A15)-Pad60)") (class "Default")
      (node (ref "U1") (pin "60") (pinfunction "PC7_(A15)_60") (pintype "bidirectional"))
    )
    (net (code "74") (name "unconnected-(U1-PD4_(ICP1)-Pad47)") (class "Default")
      (node (ref "U1") (pin "47") (pinfunction "PD4_(ICP1)_47") (pintype "bidirectional"))
    )
    (net (code "75") (name "unconnected-(U1-PD5_(XCK1)-Pad48)") (class "Default")
      (node (ref "U1") (pin "48") (pinfunction "PD5_(XCK1)_48") (pintype "bidirectional"))
    )
    (net (code "76") (name "unconnected-(U1-PD6_(T1)-Pad49)") (class "Default")
      (node (ref "U1") (pin "49") (pinfunction "PD6_(T1)_49") (pintype "bidirectional"))
    )
    (net (code "77") (name "unconnected-(U1-PD7_(T0)-Pad50)") (class "Default")
      (node (ref "U1") (pin "50") (pinfunction "PD7_(T0)_50") (pintype "bidirectional"))
    )
    (net (code "78") (name "unconnected-(U1-PE2_(XCK0{slash}AIN0)-Pad4)") (class "Default")
      (node (ref "U1") (pin "4") (pinfunction "PE2_(XCK0/AIN0)_4") (pintype "bidirectional"))
    )
    (net (code "79") (name "unconnected-(U1-PE3_(OC3A{slash}AIN1)-Pad5)") (class "Default")
      (node (ref "U1") (pin "5") (pinfunction "PE3_(OC3A/AIN1)_5") (pintype "bidirectional"))
    )
    (net (code "80") (name "unconnected-(U1-PE5_(OC3C{slash}INT5)-Pad7)") (class "Default")
      (node (ref "U1") (pin "7") (pinfunction "PE5_(OC3C/INT5)_7") (pintype "bidirectional"))
    )
    (net (code "81") (name "unconnected-(U1-PE6_(T3{slash}INT6)-Pad8)") (class "Default")
      (node (ref "U1") (pin "8") (pinfunction "PE6_(T3/INT6)_8") (pintype "bidirectional"))
    )
    (net (code "82") (name "unconnected-(U1-PE7_(CLKO{slash}ICP3{slash}INT7)-Pad9)") (class "Default")
      (node (ref "U1") (pin "9") (pinfunction "PE7_(CLKO/ICP3/INT7)_9") (pintype "bidirectional"))
    )
    (net (code "83") (name "unconnected-(U1-PG0_(WR)-Pad51)") (class "Default")
      (node (ref "U1") (pin "51") (pinfunction "PG0_(WR)_51") (pintype "bidirectional"))
    )
    (net (code "84") (name "unconnected-(U1-PG1_(RD)-Pad52)") (class "Default")
      (node (ref "U1") (pin "52") (pinfunction "PG1_(RD)_52") (pintype "bidirectional"))
    )
    (net (code "85") (name "unconnected-(U1-PG2_(ALE)-Pad70)") (class "Default")
      (node (ref "U1") (pin "70") (pinfunction "PG2_(ALE)_70") (pintype "bidirectional"))
    )
    (net (code "86") (name "unconnected-(U1-PG3_(TOSC2)-Pad28)") (class "Default")
      (node (ref "U1") (pin "28") (pinfunction "PG3_(TOSC2)_28") (pintype "bidirectional"))
    )
    (net (code "87") (name "unconnected-(U1-PG4_(TOSC1)-Pad29)") (class "Default")
      (node (ref "U1") (pin "29") (pinfunction "PG4_(TOSC1)_29") (pintype "bidirectional"))
    )
    (net (code "88") (name "unconnected-(U1-PG5_(OC0B)-Pad1)") (class "Default")
      (node (ref "U1") (pin "1") (pinfunction "PG5_(OC0B)_1") (pintype "bidirectional"))
    )
    (net (code "89") (name "unconnected-(U1-PH7_(T4)-Pad27)") (class "Default")
      (node (ref "U1") (pin "27") (pinfunction "PH7_(T4)_27") (pintype "bidirectional"))
    )
    (net (code "90") (name "unconnected-(U1-PJ2_(XCK3{slash}PCINT11)-Pad65)") (class "Default")
      (node (ref "U1") (pin "65") (pinfunction "PJ2_(XCK3/PCINT11)_65") (pintype "bidirectional"))
    )
    (net (code "91") (name "unconnected-(U1-PJ3_(PCINT12)-Pad66)") (class "Default")
      (node (ref "U1") (pin "66") (pinfunction "PJ3_(PCINT12)_66") (pintype "bidirectional"))
    )
    (net (code "92") (name "unconnected-(U1-PJ4_(PCINT13)-Pad67)") (class "Default")
      (node (ref "U1") (pin "67") (pinfunction "PJ4_(PCINT13)_67") (pintype "bidirectional"))
    )
    (net (code "93") (name "unconnected-(U1-PJ5_(PCINT14)-Pad68)") (class "Default")
      (node (ref "U1") (pin "68") (pinfunction "PJ5_(PCINT14)_68") (pintype "bidirectional"))
    )
    (net (code "94") (name "unconnected-(U1-PJ6_(PCINT15)-Pad69)") (class "Default")
      (node (ref "U1") (pin "69") (pinfunction "PJ6_(PCINT15)_69") (pintype "bidirectional"))
    )
    (net (code "95") (name "unconnected-(U1-PJ7-Pad79)") (class "Default")
      (node (ref "U1") (pin "79") (pinfunction "PJ7_79") (pintype "bidirectional"))
    )
    (net (code "96") (name "unconnected-(U1-PL0_(ICP4)-Pad35)") (class "Default")
      (node (ref "U1") (pin "35") (pinfunction "PL0_(ICP4)_35") (pintype "bidirectional"))
    )
    (net (code "97") (name "unconnected-(U1-PL1_(ICP5)-Pad36)") (class "Default")
      (node (ref "U1") (pin "36") (pinfunction "PL1_(ICP5)_36") (pintype "bidirectional"))
    )
    (net (code "98") (name "unconnected-(U1-PL6-Pad41)") (class "Default")
      (node (ref "U1") (pin "41") (pinfunction "PL6_41") (pintype "bidirectional"))
    )
    (net (code "99") (name "unconnected-(U1-PL7-Pad42)") (class "Default")
      (node (ref "U1") (pin "42") (pinfunction "PL7_42") (pintype "bidirectional"))
    )
    (net (code "100") (name "unconnected-(U2-~{EXT}-Pad4)") (class "Default")
      (node (ref "U2") (pin "4") (pinfunction "~{EXT}_4") (pintype "output"))
    )
    (net (code "101") (name "unconnected-(U3-3V3-Pad6)") (class "Default")
      (node (ref "U3") (pin "6") (pinfunction "3V3_6") (pintype "output"))
    )
    (net (code "102") (name "unconnected-(U3-KEY0-Pad12)") (class "Default")
      (node (ref "U3") (pin "12") (pinfunction "KEY0_12") (pintype "input"))
    )
    (net (code "103") (name "unconnected-(U3-KEY1-Pad13)") (class "Default")
      (node (ref "U3") (pin "13") (pinfunction "KEY1_13") (pintype "input"))
    )
    (net (code "104") (name "unconnected-(U3-KEY2-Pad14)") (class "Default")
      (node (ref "U3") (pin "14") (pinfunction "KEY2_14") (pintype "input"))
    )
    (net (code "105") (name "unconnected-(U3-KEY3-Pad15)") (class "Default")
      (node (ref "U3") (pin "15") (pinfunction "KEY3_15") (pintype "input"))
    )
    (net (code "106") (name "unconnected-(U3-KEY4-Pad16)") (class "Default")
      (node (ref "U3") (pin "16") (pinfunction "KEY4_16") (pintype "input"))
    )
    (net (code "107") (name "unconnected-(U3-KEY5-Pad17)") (class "Default")
      (node (ref "U3") (pin "17") (pinfunction "KEY5_17") (pintype "input"))
    )
    (net (code "108") (name "unconnected-(U3-KEY6-Pad18)") (class "Default")
      (node (ref "U3") (pin "18") (pinfunction "KEY6_18") (pintype "input"))
    )
    (net (code "109") (name "unconnected-(U3-KEY7-Pad19)") (class "Default")
      (node (ref "U3") (pin "19") (pinfunction "KEY7_19") (pintype "input"))
    )
    (net (code "110") (name "unconnected-(U3-KEY8-Pad20)") (class "Default")
      (node (ref "U3") (pin "20") (pinfunction "KEY8_20") (pintype "input"))
    )
    (net (code "111") (name "unconnected-(U3-KEY9-Pad21)") (class "Default")
      (node (ref "U3") (pin "21") (pinfunction "KEY9_21") (pintype "input"))
    )
    (net (code "112") (name "unconnected-(U3-KEY10-Pad22)") (class "Default")
      (node (ref "U3") (pin "22") (pinfunction "KEY10_22") (pintype "input"))
    )
    (net (code "113") (name "unconnected-(U3-KEY11-Pad23)") (class "Default")
      (node (ref "U3") (pin "23") (pinfunction "KEY11_23") (pintype "input"))
    )
    (net (code "114") (name "unconnected-(U3-L1-Pad2)") (class "Default")
      (node (ref "U3") (pin "2") (pinfunction "L1_2") (pintype "output"))
    )
    (net (code "115") (name "unconnected-(U3-PB-Pad3)") (class "Default")
      (node (ref "U3") (pin "3") (pinfunction "PB_3") (pintype "input"))
    )
    (net (code "116") (name "unconnected-(U3-RESET-Pad5)") (class "Default")
      (node (ref "U3") (pin "5") (pinfunction "RESET_5") (pintype "input"))
    )
    (net (code "117") (name "unconnected-(U4-CBUS0-Pad23)") (class "Default")
      (node (ref "U4") (pin "23") (pinfunction "CBUS0_23") (pintype "bidirectional"))
    )
    (net (code "118") (name "unconnected-(U4-CBUS1-Pad22)") (class "Default")
      (node (ref "U4") (pin "22") (pinfunction "CBUS1_22") (pintype "bidirectional"))
    )
    (net (code "119") (name "unconnected-(U4-CBUS2-Pad13)") (class "Default")
      (node (ref "U4") (pin "13") (pinfunction "CBUS2_13") (pintype "bidirectional"))
    )
    (net (code "120") (name "unconnected-(U4-CBUS3-Pad14)") (class "Default")
      (node (ref "U4") (pin "14") (pinfunction "CBUS3_14") (pintype "bidirectional"))
    )
    (net (code "121") (name "unconnected-(U4-CBUS4-Pad12)") (class "Default")
      (node (ref "U4") (pin "12") (pinfunction "CBUS4_12") (pintype "bidirectional"))
    )
    (net (code "122") (name "unconnected-(U4-NC-Pad8)") (class "Default")
      (node (ref "U4") (pin "8") (pinfunction "NC_8") (pintype "passive"))
    )
    (net (code "123") (name "unconnected-(U4-NC-Pad24)") (class "Default")
      (node (ref "U4") (pin "24") (pinfunction "NC_24") (pintype "passive"))
    )
    (net (code "124") (name "unconnected-(U4-OSCI-Pad27)") (class "Default")
      (node (ref "U4") (pin "27") (pinfunction "OSCI_27") (pintype "input"))
    )
    (net (code "125") (name "unconnected-(U4-OSCO-Pad28)") (class "Default")
      (node (ref "U4") (pin "28") (pinfunction "OSCO_28") (pintype "output"))
    )
    (net (code "126") (name "unconnected-(U4-TEST-Pad26)") (class "Default")
      (node (ref "U4") (pin "26") (pinfunction "TEST_26") (pintype "input"))
    )
    (net (code "127") (name "unconnected-(U4-~{CTS}-Pad11)") (class "Default")
      (node (ref "U4") (pin "11") (pinfunction "~{CTS}_11") (pintype "input"))
    )
    (net (code "128") (name "unconnected-(U4-~{DCD}-Pad10)") (class "Default")
      (node (ref "U4") (pin "10") (pinfunction "~{DCD}_10") (pintype "input"))
    )
    (net (code "129") (name "unconnected-(U4-~{DSR}-Pad9)") (class "Default")
      (node (ref "U4") (pin "9") (pinfunction "~{DSR}_9") (pintype "input"))
    )
    (net (code "130") (name "unconnected-(U4-~{RESET}-Pad19)") (class "Default")
      (node (ref "U4") (pin "19") (pinfunction "~{RESET}_19") (pintype "input"))
    )
    (net (code "131") (name "unconnected-(U4-~{RI}-Pad6)") (class "Default")
      (node (ref "U4") (pin "6") (pinfunction "~{RI}_6") (pintype "input"))
    )
    (net (code "132") (name "unconnected-(U4-~{RTS}-Pad3)") (class "Default")
      (node (ref "U4") (pin "3") (pinfunction "~{RTS}_3") (pintype "output"))
    )
    (net (code "133") (name "unconnected-(U5-CTS-Pad3)") (class "Default")
      (node (ref "U5") (pin "3") (pinfunction "CTS_3") (pintype "passive"))
    )
    (net (code "134") (name "unconnected-(U5-GPIO-Pad13)") (class "Default")
      (node (ref "U5") (pin "13") (pinfunction "GPIO_13") (pintype "passive"))
    )
    (net (code "135") (name "unconnected-(U5-LED-Pad15)") (class "Default")
      (node (ref "U5") (pin "15") (pinfunction "LED_15") (pintype "passive"))
    )
    (net (code "136") (name "unconnected-(U5-PWM-Pad14)") (class "Default")
      (node (ref "U5") (pin "14") (pinfunction "PWM_14") (pintype "passive"))
    )
    (net (code "137") (name "unconnected-(U5-RTS-Pad1)") (class "Default")
      (node (ref "U5") (pin "1") (pinfunction "RTS_1") (pintype "passive"))
    )
    (net (code "138") (name "unconnected-(U8-ANT-Pad15)") (class "Default")
      (node (ref "U8") (pin "15") (pinfunction "ANT_15") (pintype "tri_state"))
    )
    (net (code "139") (name "unconnected-(U8-DIO0-Pad2)") (class "Default")
      (node (ref "U8") (pin "2") (pinfunction "DIO0_2") (pintype "bidirectional"))
    )
    (net (code "140") (name "unconnected-(U8-DIO1-Pad3)") (class "Default")
      (node (ref "U8") (pin "3") (pinfunction "DIO1_3") (pintype "bidirectional"))
    )
    (net (code "141") (name "unconnected-(U8-DIO2-Pad4)") (class "Default")
      (node (ref "U8") (pin "4") (pinfunction "DIO2_4") (pintype "bidirectional"))
    )
    (net (code "142") (name "unconnected-(U8-DIO3-Pad5)") (class "Default")
      (node (ref "U8") (pin "5") (pinfunction "DIO3_5") (pintype "bidirectional"))
    )
    (net (code "143") (name "unconnected-(U8-DIO5-Pad6)") (class "Default")
      (node (ref "U8") (pin "6") (pinfunction "DIO5_6") (pintype "bidirectional"))
    )
    (net (code "144") (name "unconnected-(U8-DIO6-Pad7)") (class "Default")
      (node (ref "U8") (pin "7") (pinfunction "DIO6_7") (pintype "bidirectional"))
    )
    (net (code "145") (name "unconnected-(U8-GNDA-Pad14)") (class "Default")
      (node (ref "U8") (pin "14") (pinfunction "GNDA_14") (pintype "power_in"))
    )
    (net (code "146") (name "unconnected-(U9-DAT1-Pad8)") (class "Default")
      (node (ref "U9") (pin "8") (pinfunction "DAT1_8") (pintype "passive"))
    )
    (net (code "147") (name "unconnected-(U9-DAT2-Pad1)") (class "Default")
      (node (ref "U9") (pin "1") (pinfunction "DAT2_1") (pintype "passive"))
    )
    (net (code "148") (name "unconnected-(U10-3.3V-Pad8)") (class "Default")
      (node (ref "U10") (pin "8") (pinfunction "3.3V_8") (pintype "input"))
    )
    (net (code "149") (name "unconnected-(U10-RST-Pad7)") (class "Default")
      (node (ref "U10") (pin "7") (pinfunction "RST_7") (pintype "output"))
    )
    (net (code "150") (name "unconnected-(U12-R-Pad1)") (class "Default")
      (node (ref "U12") (pin "1") (pinfunction "R_1") (pintype "output"))
    )
  )
)
